# lm7805-power-supply.net
KiCad netlist of a schematic drawn in Altium Designer
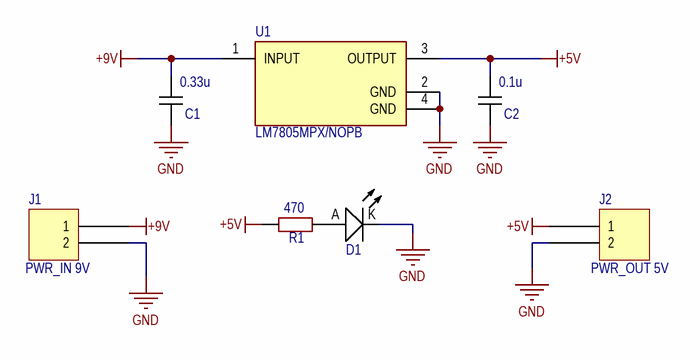
[diagram p0: lm7805-power-supply.SchDoc]

(export (version "E")
  (design (tool "Eeschema 10.0.6"))
  (components
    (comp (ref "C1")
      (value "0.33u")
      (footprint "CAP_CER_1206")
      (description "Cap Cer MLCC SMD 50V 0.33uF X7R 1206 5%")
      (fields
        (field (name "PART NUMBER") "CC1206JRX7R9BB334")
        (field (name "MOUSER PART NUMBER") "603-CC1206JR9BB334")
      )
      (libsource (lib "SssAccesDatbase") (part "Cap"))
    )
    (comp (ref "C2")
      (value "0.1u")
      (footprint "CAP_CER_1206")
      (description "Cap Cer MLCC SMD 50V 0.1uF C0G NP0 1206 5%")
      (fields
        (field (name "PART NUMBER") "C3216C0G1H104J160AA")
        (field (name "MOUSER PART NUMBER") "810-C3216C0G1H104J")
      )
      (libsource (lib "SssAccesDatbase") (part "Cap"))
    )
    (comp (ref "D1")
      (value "Bl 0603")
      (footprint "LED-0603-BLUE")
      (description "LED BLUE DIFFUSED 0603 SMD")
      (fields
        (field (name "PART NUMBER") "150060BS55040")
        (field (name "DIGI-KEY PART NUMBER") "732-12013-1-ND")
      )
      (libsource (lib "SssAccesDatbase") (part "LED_AK"))
    )
    (comp (ref "J1")
      (value "PWR_IN 9V")
      (footprint "TE 282837-2")
      (description "TERM BLK 2P SIDE ENT 5.08MM PCB")
      (fields
        (field (name "PART NUMBER") "282837-2")
        (field (name "MANUFACTURER") "TE Connectivity AMP Connectors")
      )
      (libsource (lib "Celestial Altium Library - altium_library") (part "2 Pin"))
    )
    (comp (ref "J2")
      (value "PWR_OUT 5V")
      (footprint "TE 282837-2")
      (description "TERM BLK 2P SIDE ENT 5.08MM PCB")
      (fields
        (field (name "PART NUMBER") "282837-2")
        (field (name "MANUFACTURER") "TE Connectivity AMP Connectors")
      )
      (libsource (lib "") (part "2 Pin_1"))
    )
    (comp (ref "R1")
      (value "470")
      (footprint "RESC1608(0603)N")
      (description "RES SMD 0603 470  0.5% 25ppm")
      (fields
        (field (name "PART NUMBER") "RN731JTTD4700D25")
        (field (name "MOUSER PART NUMBER") "660-RN731JTTD4700D25")
      )
      (libsource (lib "SssAccesDatbase") (part "Resistor general"))
    )
    (comp (ref "U1")
      (value "LM7805MPX/NOPB")
      (footprint "FP-LM7805MPX-NOPB-MFG")
      (description "Linear Voltage Regulator IC  1 Output  1.5A SOT-223-4")
      (fields (field (name "MANUFACTURER") "Texas Instruments"))
      (libsource (lib "Altium Content Vault") (part "b4ee7691a89d8e73302b24c49f391f2"))
    )
  )
  (nets
    (net (code "1") (name "+5V") (class "Default")
      (node (ref "C2") (pin "2") (pinfunction "2_2") (pintype "passive"))
      (node (ref "J2") (pin "1") (pinfunction "1_1") (pintype "passive"))
      (node (ref "R1") (pin "1") (pinfunction "1_1") (pintype "passive"))
      (node (ref "U1") (pin "3") (pinfunction "OUTPUT_3") (pintype "passive"))
    )
    (net (code "2") (name "+9V") (class "Default")
      (node (ref "C1") (pin "2") (pinfunction "2_2") (pintype "passive"))
      (node (ref "J1") (pin "1") (pinfunction "1_1") (pintype "passive"))
      (node (ref "U1") (pin "1") (pinfunction "INPUT_1") (pintype "power_in"))
    )
    (net (code "3") (name "GND") (class "Default")
      (node (ref "C1") (pin "1") (pinfunction "1_1") (pintype "passive"))
      (node (ref "C2") (pin "1") (pinfunction "1_1") (pintype "passive"))
      (node (ref "D1") (pin "K") (pinfunction "K_K") (pintype "passive"))
      (node (ref "J1") (pin "2") (pinfunction "2_2") (pintype "passive"))
      (node (ref "J2") (pin "2") (pinfunction "2_2") (pintype "passive"))
      (node (ref "U1") (pin "2") (pinfunction "GND_2") (pintype "power_in"))
      (node (ref "U1") (pin "4") (pinfunction "GND_4") (pintype "power_in"))
    )
    (net (code "4") (name "Net-(D1-PadA)") (class "Default")
      (node (ref "D1") (pin "A") (pinfunction "A_A") (pintype "passive"))
      (node (ref "R1") (pin "2") (pinfunction "2_2") (pintype "passive"))
    )
  )
)
